# PCB.net
KiCad netlist of a schematic drawn in EAGLE
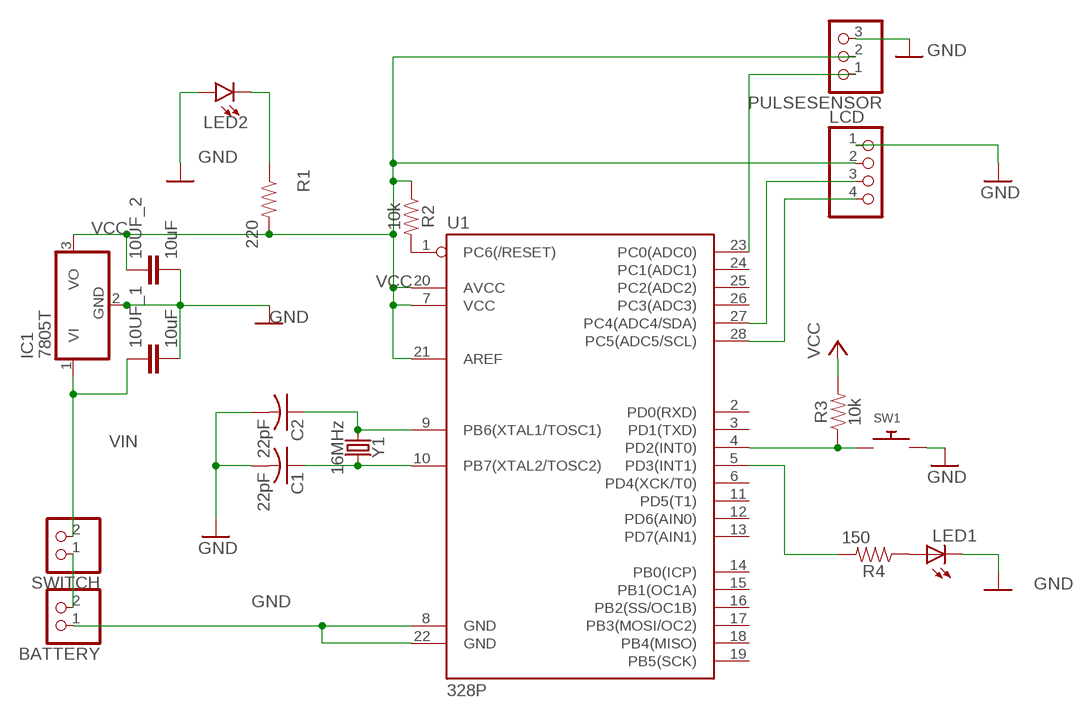
[diagram p0: schematic, sheet 1]

(export (version "E")
  (design (tool "Eeschema 10.0.6"))
  (components
    (comp (ref "10UF_1")
      (value "10uF")
      (footprint "eagle-import:CAP-PTH-2.54")
      (libsource (lib "eagle-import") (part "22PF-PTH-2.54MM-200V-5%"))
    )
    (comp (ref "10UF_2")
      (value "10uF")
      (footprint "eagle-import:CAP-PTH-2.54")
      (libsource (lib "eagle-import") (part "22PF-PTH-2.54MM-200V-5%"))
    )
    (comp (ref "BATTERY")
      (value "PINHD-1X2")
      (footprint "eagle-import:1X02")
      (libsource (lib "eagle-import") (part "PINHD-1X2"))
    )
    (comp (ref "C1")
      (value "22pF")
      (footprint "eagle-import:C025-024X044")
      (libsource (lib "eagle-import") (part "C-US025-024X044"))
    )
    (comp (ref "C2")
      (value "22pF")
      (footprint "eagle-import:C025-024X044")
      (libsource (lib "eagle-import") (part "C-US025-024X044"))
    )
    (comp (ref "IC1")
      (value "7805T")
      (footprint "eagle-import:TO220H")
      (libsource (lib "eagle-import") (part "78T05"))
    )
    (comp (ref "LCD")
      (value "PINHD-1X4")
      (footprint "eagle-import:1X04")
      (libsource (lib "eagle-import") (part "PINHD-1X4"))
    )
    (comp (ref "LED1")
      (value "LED5MM")
      (footprint "eagle-import:LED5MM")
      (libsource (lib "eagle-import") (part "adafruit_420_LED5MM"))
    )
    (comp (ref "LED2")
      (value "LED3MM")
      (footprint "eagle-import:LED_3MM")
      (libsource (lib "eagle-import") (part "LED3MM"))
    )
    (comp (ref "PULSESENSOR")
      (value "PINHD-1X3")
      (footprint "eagle-import:1X03")
      (libsource (lib "eagle-import") (part "PINHD-1X3"))
    )
    (comp (ref "R1")
      (value "220")
      (footprint "eagle-import:AXIAL-0.3")
      (libsource (lib "eagle-import") (part "10KOHM-HORIZ-1/4W-5%"))
    )
    (comp (ref "R2")
      (value "10k")
      (footprint "eagle-import:AXIAL-0.3")
      (libsource (lib "eagle-import") (part "10KOHM-HORIZ-1/4W-5%"))
    )
    (comp (ref "R3")
      (value "10k")
      (footprint "eagle-import:AXIAL-0.3")
      (libsource (lib "eagle-import") (part "10KOHM-HORIZ-1/4W-5%"))
    )
    (comp (ref "R4")
      (value "150")
      (footprint "eagle-import:AXIAL-0.3")
      (libsource (lib "eagle-import") (part "10KOHM-HORIZ-1/4W-5%"))
    )
    (comp (ref "SW1")
      (value "SWITCH_PUSHBUTTONEVQ-PE")
      (footprint "eagle-import:TACT_PANA-EVQ")
      (libsource (lib "eagle-import") (part "SWITCH_PUSHBUTTONEVQ-PE"))
    )
    (comp (ref "SWITCH")
      (value "PINHD-1X2")
      (footprint "eagle-import:1X02")
      (libsource (lib "eagle-import") (part "PINHD-1X2"))
    )
    (comp (ref "U1")
      (value "328P")
      (footprint "eagle-import:DIP28")
      (libsource (lib "eagle-import") (part "ATMEGA328P_PDIP"))
    )
    (comp (ref "Y1")
      (value "16MHz")
      (footprint "eagle-import:HC49US")
      (libsource (lib "eagle-import") (part "CRYSTAL-16MHZPTH-HC49US"))
    )
  )
  (nets
    (net (code "1") (name "/VIN") (class "Default")
      (node (ref "10UF_1") (pin "1") (pinfunction "1_1") (pintype "passive"))
      (node (ref "IC1") (pin "1") (pinfunction "VI_1") (pintype "input"))
      (node (ref "SWITCH") (pin "2") (pinfunction "2_2") (pintype "passive"))
    )
    (net (code "2") (name "GND") (class "Default")
      (node (ref "10UF_1") (pin "2") (pinfunction "2_2") (pintype "passive"))
      (node (ref "10UF_2") (pin "2") (pinfunction "2_2") (pintype "passive"))
      (node (ref "BATTERY") (pin "1") (pinfunction "1_1") (pintype "passive"))
      (node (ref "C1") (pin "2") (pinfunction "2_2") (pintype "passive"))
      (node (ref "C2") (pin "2") (pinfunction "2_2") (pintype "passive"))
      (node (ref "IC1") (pin "2") (pinfunction "GND_2") (pintype "passive"))
      (node (ref "LCD") (pin "1") (pinfunction "1_1") (pintype "passive"))
      (node (ref "LED1") (pin "K") (pinfunction "C_K") (pintype "passive"))
      (node (ref "LED2") (pin "A") (pinfunction "A_A") (pintype "passive"))
      (node (ref "PULSESENSOR") (pin "3") (pinfunction "3_3") (pintype "passive"))
      (node (ref "SW1") (pin "P$2") (pinfunction "P$2_P$2") (pintype "passive"))
      (node (ref "U1") (pin "22") (pinfunction "GND_22") (pintype "bidirectional"))
      (node (ref "U1") (pin "8") (pinfunction "GND_8") (pintype "bidirectional"))
    )
    (net (code "3") (name "Net-(BATTERY-Pad2)") (class "Default")
      (node (ref "BATTERY") (pin "2") (pinfunction "2_2") (pintype "passive"))
      (node (ref "SWITCH") (pin "1") (pinfunction "1_1") (pintype "passive"))
    )
    (net (code "4") (name "Net-(LED2-C)") (class "Default")
      (node (ref "LED2") (pin "K") (pinfunction "C_K") (pintype "passive"))
      (node (ref "R1") (pin "P$1") (pinfunction "1_P$1") (pintype "passive"))
    )
    (net (code "5") (name "Net-(R2-2)") (class "Default")
      (node (ref "R2") (pin "P$2") (pinfunction "2_P$2") (pintype "passive"))
      (node (ref "U1") (pin "1") (pinfunction "PC6(/RESET)_1") (pintype "bidirectional"))
    )
    (net (code "6") (name "Net-(R3-1)") (class "Default")
      (node (ref "R3") (pin "P$1") (pinfunction "1_P$1") (pintype "passive"))
      (node (ref "SW1") (pin "P$1") (pinfunction "P$1_P$1") (pintype "passive"))
      (node (ref "U1") (pin "4") (pinfunction "PD2(INT0)_4") (pintype "bidirectional"))
    )
    (net (code "7") (name "Net-(R4-1)") (class "Default")
      (node (ref "LED1") (pin "A") (pinfunction "A_A") (pintype "passive"))
      (node (ref "R4") (pin "P$1") (pinfunction "1_P$1") (pintype "passive"))
    )
    (net (code "8") (name "Net-(R4-2)") (class "Default")
      (node (ref "R4") (pin "P$2") (pinfunction "2_P$2") (pintype "passive"))
      (node (ref "U1") (pin "5") (pinfunction "PD3(INT1)_5") (pintype "bidirectional"))
    )
    (net (code "9") (name "Net-(U1-PB6(XTAL1{slash}TOSC1))") (class "Default")
      (node (ref "C2") (pin "1") (pinfunction "1_1") (pintype "passive"))
      (node (ref "U1") (pin "9") (pinfunction "PB6(XTAL1/TOSC1)_9") (pintype "bidirectional"))
      (node (ref "Y1") (pin "1") (pinfunction "1_1") (pintype "passive"))
    )
    (net (code "10") (name "Net-(U1-PB7(XTAL2{slash}TOSC2))") (class "Default")
      (node (ref "C1") (pin "1") (pinfunction "1_1") (pintype "passive"))
      (node (ref "U1") (pin "10") (pinfunction "PB7(XTAL2/TOSC2)_10") (pintype "bidirectional"))
      (node (ref "Y1") (pin "2") (pinfunction "2_2") (pintype "passive"))
    )
    (net (code "11") (name "Net-(U1-PC0(ADC0))") (class "Default")
      (node (ref "PULSESENSOR") (pin "1") (pinfunction "1_1") (pintype "passive"))
      (node (ref "U1") (pin "23") (pinfunction "PC0(ADC0)_23") (pintype "bidirectional"))
    )
    (net (code "12") (name "Net-(U1-PC4(ADC4{slash}SDA))") (class "Default")
      (node (ref "LCD") (pin "3") (pinfunction "3_3") (pintype "passive"))
      (node (ref "U1") (pin "27") (pinfunction "PC4(ADC4/SDA)_27") (pintype "bidirectional"))
    )
    (net (code "13") (name "Net-(U1-PC5(ADC5{slash}SCL))") (class "Default")
      (node (ref "LCD") (pin "4") (pinfunction "4_4") (pintype "passive"))
      (node (ref "U1") (pin "28") (pinfunction "PC5(ADC5/SCL)_28") (pintype "bidirectional"))
    )
    (net (code "14") (name "VCC") (class "Default")
      (node (ref "10UF_2") (pin "1") (pinfunction "1_1") (pintype "passive"))
      (node (ref "IC1") (pin "3") (pinfunction "VO_3") (pintype "passive"))
      (node (ref "LCD") (pin "2") (pinfunction "2_2") (pintype "passive"))
      (node (ref "PULSESENSOR") (pin "2") (pinfunction "2_2") (pintype "passive"))
      (node (ref "R1") (pin "P$2") (pinfunction "2_P$2") (pintype "passive"))
      (node (ref "R2") (pin "P$1") (pinfunction "1_P$1") (pintype "passive"))
      (node (ref "R3") (pin "P$2") (pinfunction "2_P$2") (pintype "passive"))
      (node (ref "U1") (pin "20") (pinfunction "AVCC_20") (pintype "bidirectional"))
      (node (ref "U1") (pin "21") (pinfunction "AREF_21") (pintype "bidirectional"))
      (node (ref "U1") (pin "7") (pinfunction "VCC_7") (pintype "bidirectional"))
    )
    (net (code "15") (name "unconnected-(U1-PB0(ICP)-Pad14)") (class "Default")
      (node (ref "U1") (pin "14") (pinfunction "PB0(ICP)_14") (pintype "bidirectional"))
    )
    (net (code "16") (name "unconnected-(U1-PB1(OC1A)-Pad15)") (class "Default")
      (node (ref "U1") (pin "15") (pinfunction "PB1(OC1A)_15") (pintype "bidirectional"))
    )
    (net (code "17") (name "unconnected-(U1-PB2(SS{slash}OC1B)-Pad16)") (class "Default")
      (node (ref "U1") (pin "16") (pinfunction "PB2(SS/OC1B)_16") (pintype "bidirectional"))
    )
    (net (code "18") (name "unconnected-(U1-PB3(MOSI{slash}OC2)-Pad17)") (class "Default")
      (node (ref "U1") (pin "17") (pinfunction "PB3(MOSI/OC2)_17") (pintype "bidirectional"))
    )
    (net (code "19") (name "unconnected-(U1-PB4(MISO)-Pad18)") (class "Default")
      (node (ref "U1") (pin "18") (pinfunction "PB4(MISO)_18") (pintype "bidirectional"))
    )
    (net (code "20") (name "unconnected-(U1-PB5(SCK)-Pad19)") (class "Default")
      (node (ref "U1") (pin "19") (pinfunction "PB5(SCK)_19") (pintype "bidirectional"))
    )
    (net (code "21") (name "unconnected-(U1-PC1(ADC1)-Pad24)") (class "Default")
      (node (ref "U1") (pin "24") (pinfunction "PC1(ADC1)_24") (pintype "bidirectional"))
    )
    (net (code "22") (name "unconnected-(U1-PC2(ADC2)-Pad25)") (class "Default")
      (node (ref "U1") (pin "25") (pinfunction "PC2(ADC2)_25") (pintype "bidirectional"))
    )
    (net (code "23") (name "unconnected-(U1-PC3(ADC3)-Pad26)") (class "Default")
      (node (ref "U1") (pin "26") (pinfunction "PC3(ADC3)_26") (pintype "bidirectional"))
    )
    (net (code "24") (name "unconnected-(U1-PD0(RXD)-Pad2)") (class "Default")
      (node (ref "U1") (pin "2") (pinfunction "PD0(RXD)_2") (pintype "bidirectional"))
    )
    (net (code "25") (name "unconnected-(U1-PD1(TXD)-Pad3)") (class "Default")
      (node (ref "U1") (pin "3") (pinfunction "PD1(TXD)_3") (pintype "bidirectional"))
    )
    (net (code "26") (name "unconnected-(U1-PD4(XCK{slash}T0)-Pad6)") (class "Default")
      (node (ref "U1") (pin "6") (pinfunction "PD4(XCK/T0)_6") (pintype "bidirectional"))
    )
    (net (code "27") (name "unconnected-(U1-PD5(T1)-Pad11)") (class "Default")
      (node (ref "U1") (pin "11") (pinfunction "PD5(T1)_11") (pintype "bidirectional"))
    )
    (net (code "28") (name "unconnected-(U1-PD6(AIN0)-Pad12)") (class "Default")
      (node (ref "U1") (pin "12") (pinfunction "PD6(AIN0)_12") (pintype "bidirectional"))
    )
    (net (code "29") (name "unconnected-(U1-PD7(AIN1)-Pad13)") (class "Default")
      (node (ref "U1") (pin "13") (pinfunction "PD7(AIN1)_13") (pintype "bidirectional"))
    )
  )
)
